# communication.net
KiCad netlist of a schematic drawn in Altium Designer
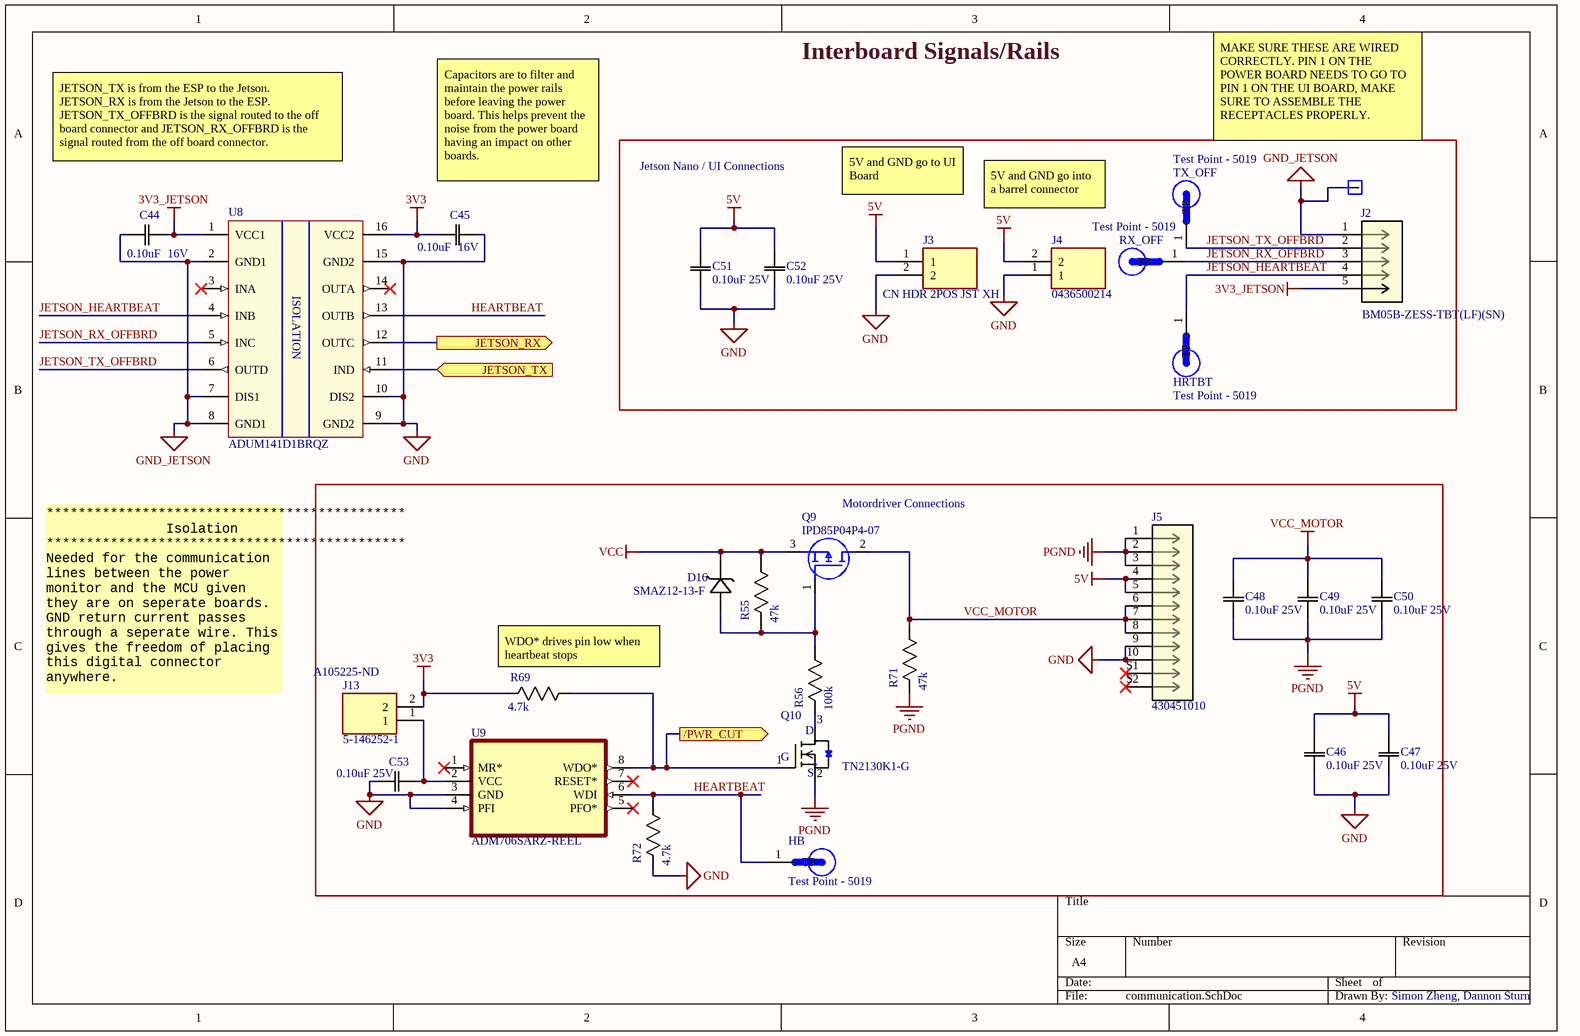
[diagram p0: communication.SchDoc]

(export (version "E")
  (design (tool "Eeschema 10.0.6"))
  (components
    (comp (ref "C44")
      (value "0.10uF")
      (footprint "0603")
      (description "CAP CER 0.10UF 16V X5R 0603")
      (fields
        (field (name "TOLERANCE") "10%")
        (field (name "RATING") "16V")
        (field (name "PART NUMBER") "CAP 0.10uF 16V")
      )
      (libsource (lib "capacitor_library") (part "CAP 0.10uF 16V"))
    )
    (comp (ref "C45")
      (value "0.10uF")
      (footprint "0603")
      (description "CAP CER 0.10UF 16V X5R 0603")
      (fields
        (field (name "TOLERANCE") "10%")
        (field (name "RATING") "16V")
        (field (name "PART NUMBER") "CAP 0.10uF 16V")
      )
      (libsource (lib "capacitor_library") (part "CAP 0.10uF 16V"))
    )
    (comp (ref "C46")
      (value "0.10uF 25V")
      (footprint "0603")
      (description "CAP CER 0.10UF 25V X7R 0603")
      (fields (field (name "TOLERANCE") "10%") (field (name "PART NUMBER") "CAP 0.10uF 25V"))
      (libsource (lib "capacitor_library") (part "CAP 0.10uF 25V"))
    )
    (comp (ref "C47")
      (value "0.10uF 25V")
      (footprint "0603")
      (description "CAP CER 0.10UF 25V X7R 0603")
      (fields (field (name "TOLERANCE") "10%") (field (name "PART NUMBER") "CAP 0.10uF 25V"))
      (libsource (lib "capacitor_library") (part "CAP 0.10uF 25V"))
    )
    (comp (ref "C48")
      (value "0.10uF 25V")
      (footprint "0603")
      (description "CAP CER 0.10UF 25V X7R 0603")
      (fields (field (name "TOLERANCE") "10%") (field (name "PART NUMBER") "CAP 0.10uF 25V"))
      (libsource (lib "capacitor_library") (part "CAP 0.10uF 25V"))
    )
    (comp (ref "C49")
      (value "0.10uF 25V")
      (footprint "0603")
      (description "CAP CER 0.10UF 25V X7R 0603")
      (fields (field (name "TOLERANCE") "10%") (field (name "PART NUMBER") "CAP 0.10uF 25V"))
      (libsource (lib "capacitor_library") (part "CAP 0.10uF 25V"))
    )
    (comp (ref "C50")
      (value "0.10uF 25V")
      (footprint "0603")
      (description "CAP CER 0.10UF 25V X7R 0603")
      (fields (field (name "TOLERANCE") "10%") (field (name "PART NUMBER") "CAP 0.10uF 25V"))
      (libsource (lib "capacitor_library") (part "CAP 0.10uF 25V"))
    )
    (comp (ref "C51")
      (value "0.10uF 25V")
      (footprint "0603")
      (description "CAP CER 0.10UF 25V X7R 0603")
      (fields (field (name "TOLERANCE") "10%") (field (name "PART NUMBER") "CAP 0.10uF 25V"))
      (libsource (lib "capacitor_library") (part "CAP 0.10uF 25V"))
    )
    (comp (ref "C52")
      (value "0.10uF 25V")
      (footprint "0603")
      (description "CAP CER 0.10UF 25V X7R 0603")
      (fields (field (name "TOLERANCE") "10%") (field (name "PART NUMBER") "CAP 0.10uF 25V"))
      (libsource (lib "capacitor_library") (part "CAP 0.10uF 25V"))
    )
    (comp (ref "C53")
      (value "0.10uF 25V")
      (footprint "0603")
      (description "CAP CER 0.10UF 25V X7R 0603")
      (fields (field (name "TOLERANCE") "10%") (field (name "PART NUMBER") "CAP 0.10uF 25V"))
      (libsource (lib "capacitor_library") (part "CAP 0.10uF 25V"))
    )
    (comp (ref "D16")
      (value "SMAZ12-13-F")
      (footprint "SMA_DIO-L")
      (description "Zener Diode 12 V 1 W ±5% Surface Mount SMA")
      (fields
        (field (name "PART NUMBER") "DIODE ZENER 12V 1W")
        (field (name "COPYRIGHT") "Copyright (C) 2021 Ultra Librarian. All rights reserved.")
      )
      (libsource (lib "Diode_Library") (part "DIODE ZENER 12V 1W"))
    )
    (comp (ref "HB")
      (value "Test Point - 5019")
      (footprint "TP380X203")
      (description "PC Test Point, Miniature Phosphor Bronze, Silver Plating Surface Mount Mounting Type")
      (fields (field (name "MP") "5019") (field (name "MF") "Keystone Electronics"))
      (libsource (lib "IC_Library") (part "Test Point - 5019"))
    )
    (comp (ref "HRTBT")
      (value "Test Point - 5019")
      (footprint "TP380X203")
      (description "PC Test Point, Miniature Phosphor Bronze, Silver Plating Surface Mount Mounting Type")
      (fields (field (name "MP") "5019") (field (name "MF") "Keystone Electronics"))
      (libsource (lib "IC_Library") (part "Test Point - 5019"))
    )
    (comp (ref "J2")
      (value "BM05B-ZESS-TBT(LF)(SN)")
      (footprint "JST ZE SMT 5POS")
      (description "CONN HEADER VERT SMD 5POS ZE")
      (fields (field (name "PART NUMBER") "CN 5POS JST ZE SMT"))
      (libsource (lib "Connector_Library") (part "CN 5POS JST ZE SMT"))
    )
    (comp (ref "J3")
      (value "CN HDR 2POS JST XH")
      (footprint "JST_B2B-XH-A(LF)(SN)")
      (description "Connector Header Through Hole 2 position 0.098 _2.50mm_\r\nJST XH")
      (fields (field (name "MP") "B2B-XH-A_LF__SN_") (field (name "MF") "JST Sales"))
      (libsource (lib "Connector_Library") (part "CN HDR 2POS JST XH"))
    )
    (comp (ref "J4")
      (value "0436500214")
      (footprint "43650-0214")
      (description "Connector Header Surface Mount, Right Angle 2 position 0.118\" (3.00mm)")
      (fields
        (field (name "MANUFACTURER_PART_NUMBER") "43650-0214")
        (field (name "PART NUMBER") "CN HDR 2POS Molex 0436500214")
      )
      (libsource (lib "Connector_Library") (part "CN HDR 2POS Molex 0436500214"))
    )
    (comp (ref "J5")
      (value "430451010")
      (footprint "CON_430451010_MOL")
      (description "Connector Header Surface Mount, Right Angle 10 position 0.118\" (3.00mm)")
      (fields
        (field (name "PART NUMBER") "CN HDR 10POS MOLEX 430451010")
        (field (name "COPYRIGHT") "Copyright (C) 2021 Ultra Librarian. All rights reserved.")
      )
      (libsource (lib "Connector_Library") (part "CN HDR 10POS MOLEX 430451010"))
    )
    (comp (ref "J13")
      (value "5-146252-1")
      (footprint "TE_5-146252-1")
      (description "2 Pin Jumper Male Pins and Cap")
      (fields (field (name "SUPPLIER PART NUMBER 1") "A105225-ND"))
      (libsource (lib "Connector_Library") (part "5-146252-1"))
    )
    (comp (ref "JETSON_GND")
      (value "Breakout Pin 0603")
      (footprint "BreakoutPin 0603")
      (description "0603 breakout pad")
      (libsource (lib "IC_Library") (part "Breakout Pin 0603"))
    )
    (comp (ref "Q9")
      (value "IPD85P04P4-07")
      (footprint "DPAK (TO-252)")
      (description "P-Channel 40 V 85A (Tc) 88W (Tc) Surface Mount PG-TO252-3-313")
      (fields (field (name "PART NUMBER") "MOSFET IPD85P04P4-07"))
      (libsource (lib "Transistor_Library") (part "MOSFET IPD85P04P4-07"))
    )
    (comp (ref "Q10")
      (value "TN2130K1-G")
      (footprint "SOT95P237X112-3N")
      (description "N-Channel 300 V 85mA (Tj) 360mW (Tc) Surface Mount TO-236AB (SOT23)")
      (fields
        (field (name "PART NUMBER") "MOSFET N-CH TN2130K1-G")
        (field (name "COPYRIGHT") "Copyright (C) 2021 Ultra Librarian. All rights reserved.")
      )
      (libsource (lib "Transistor_Library") (part "MOSFET N-CH TN2130K1-G"))
    )
    (comp (ref "R55")
      (value "47k")
      (footprint "0603")
      (description "RES SMD 47k OHM 5% 1/8W 0603")
      (fields (field (name "TOLERANCE") "5%") (field (name "PART NUMBER") "RES 47k 1/8W - 5%"))
      (libsource (lib "Resistor_Library") (part "RES 47k 1/8W - 5%"))
    )
    (comp (ref "R56")
      (value "100k")
      (footprint "0603")
      (description "RES SMD 100K OHM 5% 1/8W 0603")
      (fields (field (name "TOLERANCE") "5%") (field (name "PART NUMBER") "RES 100k 1/8W - 5%"))
      (libsource (lib "Resistor_Library") (part "RES 100k 1/8W 5%"))
    )
    (comp (ref "R69")
      (value "4.7k")
      (footprint "0603")
      (description "RES SMD 4.7k OHM 5% 1/8W 0603")
      (fields (field (name "TOLERANCE") "5%") (field (name "PART NUMBER") "RES 4.7k 1/8W - 5%"))
      (libsource (lib "Resistor_Library") (part "RES 4.7k 1/8W - 5%"))
    )
    (comp (ref "R71")
      (value "47k")
      (footprint "0603")
      (description "RES SMD 47k OHM 5% 1/8W 0603")
      (fields (field (name "TOLERANCE") "5%") (field (name "PART NUMBER") "RES 47k 1/8W - 5%"))
      (libsource (lib "Resistor_Library") (part "RES 47k 1/8W - 5%"))
    )
    (comp (ref "R72")
      (value "4.7k")
      (footprint "0603")
      (description "RES SMD 4.7k OHM 5% 1/8W 0603")
      (fields (field (name "TOLERANCE") "5%") (field (name "PART NUMBER") "RES 4.7k 1/8W - 5%"))
      (libsource (lib "Resistor_Library") (part "RES 4.7k 1/8W - 5%"))
    )
    (comp (ref "RX_OFF")
      (value "Test Point - 5019")
      (footprint "TP380X203")
      (description "PC Test Point, Miniature Phosphor Bronze, Silver Plating Surface Mount Mounting Type")
      (fields (field (name "MP") "5019") (field (name "MF") "Keystone Electronics"))
      (libsource (lib "IC_Library") (part "Test Point - 5019"))
    )
    (comp (ref "TX_OFF")
      (value "Test Point - 5019")
      (footprint "TP380X203")
      (description "PC Test Point, Miniature Phosphor Bronze, Silver Plating Surface Mount Mounting Type")
      (fields (field (name "MP") "5019") (field (name "MF") "Keystone Electronics"))
      (libsource (lib "IC_Library") (part "Test Point - 5019"))
    )
    (comp (ref "U8")
      (value "ADUM141D1BRQZ")
      (footprint "SOP64P600X175-16N")
      (description "Digital Isolator CMOS 4-CH 150Mbps 16-Pin QSOP T/R")
      (fields (field (name "PART NUMBER") "ISO ADUM141D1BRQZ"))
      (libsource (lib "IC_Library") (part "ISO ADUM141D1BRQZ"))
    )
    (comp (ref "U9")
      (value "ADM706SARZ-REEL")
      (footprint "SOIC127P600X175-8N")
      (fields
        (field (name "DIGI-KEY_PART_NUMBER") "ADM706SARZ-REELCT-ND")
        (field (name "MF") "Analog Devices")
      )
      (libsource (lib "IC_Library") (part "ADM706SARZ-REEL"))
    )
  )
  (nets
    (net (code "1") (name "/HEARTBEAT") (class "Default")
      (node (ref "HB") (pin "1") (pinfunction "TP_1") (pintype "passive"))
      (node (ref "R72") (pin "1") (pinfunction "R1_1") (pintype "passive"))
      (node (ref "U8") (pin "13") (pinfunction "OUTB_13") (pintype "output"))
      (node (ref "U9") (pin "6") (pinfunction "WDI_6") (pintype "input"))
    )
    (net (code "2") (name "/JETSON_HEARTBEAT") (class "Default")
      (node (ref "HRTBT") (pin "1") (pinfunction "TP_1") (pintype "passive"))
      (node (ref "J2") (pin "4") (pinfunction "4_4") (pintype "passive"))
      (node (ref "U8") (pin "4") (pinfunction "INB_4") (pintype "input"))
    )
    (net (code "3") (name "/JETSON_RX") (class "Default")
      (node (ref "U8") (pin "12") (pinfunction "OUTC_12") (pintype "output"))
    )
    (net (code "4") (name "/JETSON_RX_OFFBRD") (class "Default")
      (node (ref "J2") (pin "3") (pinfunction "3_3") (pintype "passive"))
      (node (ref "RX_OFF") (pin "1") (pinfunction "TP_1") (pintype "passive"))
      (node (ref "U8") (pin "5") (pinfunction "INC_5") (pintype "input"))
    )
    (net (code "5") (name "/JETSON_TX") (class "Default")
      (node (ref "U8") (pin "11") (pinfunction "IND_11") (pintype "input"))
    )
    (net (code "6") (name "/JETSON_TX_OFFBRD") (class "Default")
      (node (ref "J2") (pin "2") (pinfunction "2_2") (pintype "passive"))
      (node (ref "TX_OFF") (pin "1") (pinfunction "TP_1") (pintype "passive"))
      (node (ref "U8") (pin "6") (pinfunction "OUTD_6") (pintype "output"))
    )
    (net (code "7") (name "/{slash}PWR_CUT") (class "Default")
      (node (ref "Q10") (pin "1") (pinfunction "G_1") (pintype "passive"))
      (node (ref "R69") (pin "1") (pinfunction "R1_1") (pintype "passive"))
      (node (ref "U9") (pin "8") (pinfunction "WDO*_8") (pintype "output"))
    )
    (net (code "8") (name "3V3") (class "Default")
      (node (ref "C45") (pin "2") (pinfunction "C2_2") (pintype "passive"))
      (node (ref "J13") (pin "2") (pinfunction "2_2") (pintype "passive"))
      (node (ref "R69") (pin "2") (pinfunction "R2_2") (pintype "passive"))
      (node (ref "U8") (pin "16") (pinfunction "VCC2_16") (pintype "power_in"))
    )
    (net (code "9") (name "3V3_JETSON") (class "Default")
      (node (ref "C44") (pin "2") (pinfunction "C2_2") (pintype "passive"))
      (node (ref "J2") (pin "5") (pinfunction "5_5") (pintype "passive"))
      (node (ref "U8") (pin "1") (pinfunction "VCC1_1") (pintype "power_in"))
    )
    (net (code "10") (name "5V") (class "Default")
      (node (ref "C46") (pin "2") (pinfunction "C2_2") (pintype "passive"))
      (node (ref "C47") (pin "2") (pinfunction "C2_2") (pintype "passive"))
      (node (ref "C51") (pin "2") (pinfunction "C2_2") (pintype "passive"))
      (node (ref "C52") (pin "2") (pinfunction "C2_2") (pintype "passive"))
      (node (ref "J3") (pin "1") (pinfunction "1_1") (pintype "passive"))
      (node (ref "J4") (pin "2") (pinfunction "2_2") (pintype "passive"))
      (node (ref "J5") (pin "4") (pinfunction "4_4") (pintype "passive"))
      (node (ref "J5") (pin "5") (pinfunction "5_5") (pintype "passive"))
    )
    (net (code "11") (name "GND") (class "Default")
      (node (ref "C45") (pin "1") (pinfunction "C1_1") (pintype "passive"))
      (node (ref "C46") (pin "1") (pinfunction "C1_1") (pintype "passive"))
      (node (ref "C47") (pin "1") (pinfunction "C1_1") (pintype "passive"))
      (node (ref "C51") (pin "1") (pinfunction "C1_1") (pintype "passive"))
      (node (ref "C52") (pin "1") (pinfunction "C1_1") (pintype "passive"))
      (node (ref "C53") (pin "1") (pinfunction "C1_1") (pintype "passive"))
      (node (ref "J3") (pin "2") (pinfunction "2_2") (pintype "passive"))
      (node (ref "J4") (pin "1") (pinfunction "1_1") (pintype "passive"))
      (node (ref "J5") (pin "10") (pinfunction "10_10") (pintype "passive"))
      (node (ref "J5") (pin "9") (pinfunction "9_9") (pintype "passive"))
      (node (ref "R72") (pin "2") (pinfunction "R2_2") (pintype "passive"))
      (node (ref "U8") (pin "10") (pinfunction "DIS2_10") (pintype "passive"))
      (node (ref "U8") (pin "15") (pinfunction "GND2_15") (pintype "power_in"))
      (node (ref "U8") (pin "9") (pinfunction "GND2_9") (pintype "power_in"))
      (node (ref "U9") (pin "3") (pinfunction "GND_3") (pintype "passive"))
      (node (ref "U9") (pin "4") (pinfunction "PFI_4") (pintype "input"))
    )
    (net (code "12") (name "GND_JETSON") (class "Default")
      (node (ref "C44") (pin "1") (pinfunction "C1_1") (pintype "passive"))
      (node (ref "J2") (pin "1") (pinfunction "1_1") (pintype "passive"))
      (node (ref "JETSON_GND") (pin "1") (pinfunction "BRKOUT_1") (pintype "passive"))
      (node (ref "U8") (pin "2") (pinfunction "GND1_2") (pintype "power_in"))
      (node (ref "U8") (pin "7") (pinfunction "DIS1_7") (pintype "passive"))
      (node (ref "U8") (pin "8") (pinfunction "GND1_8") (pintype "power_in"))
    )
    (net (code "13") (name "Net-(C53-C2)") (class "Default")
      (node (ref "C53") (pin "2") (pinfunction "C2_2") (pintype "passive"))
      (node (ref "J13") (pin "1") (pinfunction "1_1") (pintype "passive"))
      (node (ref "U9") (pin "2") (pinfunction "VCC_2") (pintype "power_in"))
    )
    (net (code "14") (name "Net-(Q9-G)") (class "Default")
      (node (ref "D16") (pin "2") (pinfunction "2_2") (pintype "passive"))
      (node (ref "Q9") (pin "1") (pinfunction "G_1") (pintype "passive"))
      (node (ref "R55") (pin "2") (pinfunction "R2_2") (pintype "passive"))
      (node (ref "R56") (pin "1") (pinfunction "R1_1") (pintype "passive"))
    )
    (net (code "15") (name "Net-(Q10-D)") (class "Default")
      (node (ref "Q10") (pin "3") (pinfunction "D_3") (pintype "passive"))
      (node (ref "R56") (pin "2") (pinfunction "R2_2") (pintype "passive"))
    )
    (net (code "16") (name "PGND") (class "Default")
      (node (ref "C48") (pin "1") (pinfunction "C1_1") (pintype "passive"))
      (node (ref "C49") (pin "1") (pinfunction "C1_1") (pintype "passive"))
      (node (ref "C50") (pin "1") (pinfunction "C1_1") (pintype "passive"))
      (node (ref "J5") (pin "1") (pinfunction "1_1") (pintype "passive"))
      (node (ref "J5") (pin "2") (pinfunction "2_2") (pintype "passive"))
      (node (ref "J5") (pin "3") (pinfunction "3_3") (pintype "passive"))
      (node (ref "Q10") (pin "2") (pinfunction "S_2") (pintype "passive"))
      (node (ref "R71") (pin "2") (pinfunction "R2_2") (pintype "passive"))
    )
    (net (code "17") (name "VCC") (class "Default")
      (node (ref "D16") (pin "1") (pinfunction "1_1") (pintype "passive"))
      (node (ref "Q9") (pin "3") (pinfunction "S_3") (pintype "passive"))
      (node (ref "R55") (pin "1") (pinfunction "R1_1") (pintype "passive"))
    )
    (net (code "18") (name "VCC_MOTOR") (class "Default")
      (node (ref "C48") (pin "2") (pinfunction "C2_2") (pintype "passive"))
      (node (ref "C49") (pin "2") (pinfunction "C2_2") (pintype "passive"))
      (node (ref "C50") (pin "2") (pinfunction "C2_2") (pintype "passive"))
      (node (ref "J5") (pin "6") (pinfunction "6_6") (pintype "passive"))
      (node (ref "J5") (pin "7") (pinfunction "7_7") (pintype "passive"))
      (node (ref "J5") (pin "8") (pinfunction "8_8") (pintype "passive"))
      (node (ref "Q9") (pin "2") (pinfunction "D_2") (pintype "passive"))
      (node (ref "R71") (pin "1") (pinfunction "R1_1") (pintype "passive"))
    )
    (net (code "19") (name "unconnected-(J5-PadS1)") (class "Default")
      (node (ref "J5") (pin "S1") (pinfunction "S1_S1") (pintype "passive+no_connect"))
    )
    (net (code "20") (name "unconnected-(J5-PadS2)") (class "Default")
      (node (ref "J5") (pin "S2") (pinfunction "S2_S2") (pintype "passive+no_connect"))
    )
    (net (code "21") (name "unconnected-(U8-INA-Pad3)") (class "Default")
      (node (ref "U8") (pin "3") (pinfunction "INA_3") (pintype "input+no_connect"))
    )
    (net (code "22") (name "unconnected-(U8-OUTA-Pad14)") (class "Default")
      (node (ref "U8") (pin "14") (pinfunction "OUTA_14") (pintype "output+no_connect"))
    )
    (net (code "23") (name "unconnected-(U9-MR*-Pad1)") (class "Default")
      (node (ref "U9") (pin "1") (pinfunction "MR*_1") (pintype "input+no_connect"))
    )
    (net (code "24") (name "unconnected-(U9-PFO*-Pad5)") (class "Default")
      (node (ref "U9") (pin "5") (pinfunction "PFO*_5") (pintype "output+no_connect"))
    )
    (net (code "25") (name "unconnected-(U9-RESET*-Pad7)") (class "Default")
      (node (ref "U9") (pin "7") (pinfunction "RESET*_7") (pintype "output+no_connect"))
    )
  )
)
